# Sensor4.net
KiCad netlist of a schematic drawn in EAGLE
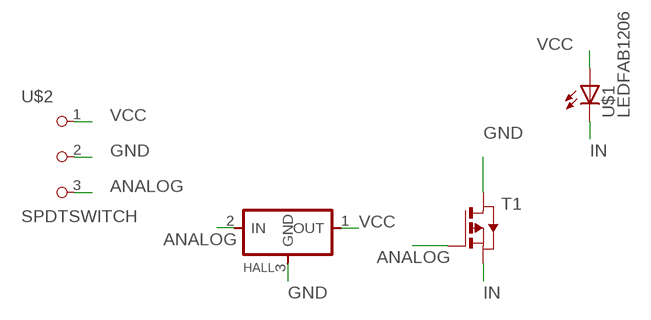
[diagram p0: schematic, sheet 1]

(export (version "E")
  (design (tool "Eeschema 10.0.6"))
  (components
    (comp (ref "HALL")
      (value "REGULATORSOT23")
      (footprint "eagle-import:SOT23")
      (libsource (lib "eagle-import") (part "REGULATORSOT23"))
    )
    (comp (ref "T1")
      (value "PMOSFETSOT23")
      (footprint "eagle-import:SOT-23")
      (libsource (lib "eagle-import") (part "PMOSFETSOT23"))
    )
    (comp (ref "U$1")
      (value "LEDFAB1206")
      (footprint "eagle-import:LED1206FAB")
      (libsource (lib "eagle-import") (part "LEDFAB1206"))
    )
    (comp (ref "U$2")
      (value "SPDTSWITCH")
      (footprint "eagle-import:SPDTSWITCH")
      (libsource (lib "eagle-import") (part "SPDTSWITCH"))
    )
  )
  (nets
    (net (code "1") (name "/ANALOG") (class "Default")
      (node (ref "HALL") (pin "2") (pinfunction "IN_2") (pintype "bidirectional"))
      (node (ref "T1") (pin "3") (pinfunction "G_3") (pintype "passive"))
      (node (ref "U$2") (pin "3") (pinfunction "3_3") (pintype "passive"))
    )
    (net (code "2") (name "/GND") (class "Default")
      (node (ref "HALL") (pin "3") (pinfunction "GND_3") (pintype "bidirectional"))
      (node (ref "T1") (pin "1") (pinfunction "D_1") (pintype "passive"))
      (node (ref "U$2") (pin "2") (pinfunction "2_2") (pintype "passive"))
    )
    (net (code "3") (name "/IN") (class "Default")
      (node (ref "T1") (pin "2") (pinfunction "S_2") (pintype "passive"))
      (node (ref "U$1") (pin "2") (pinfunction "C_2") (pintype "passive"))
    )
    (net (code "4") (name "/VCC") (class "Default")
      (node (ref "HALL") (pin "1") (pinfunction "OUT_1") (pintype "bidirectional"))
      (node (ref "U$1") (pin "1") (pinfunction "A_1") (pintype "passive"))
      (node (ref "U$2") (pin "1") (pinfunction "1_1") (pintype "passive"))
    )
  )
)
